# Relay-Board_Rack-PDU_1_0.net
KiCad netlist of a schematic drawn in EAGLE
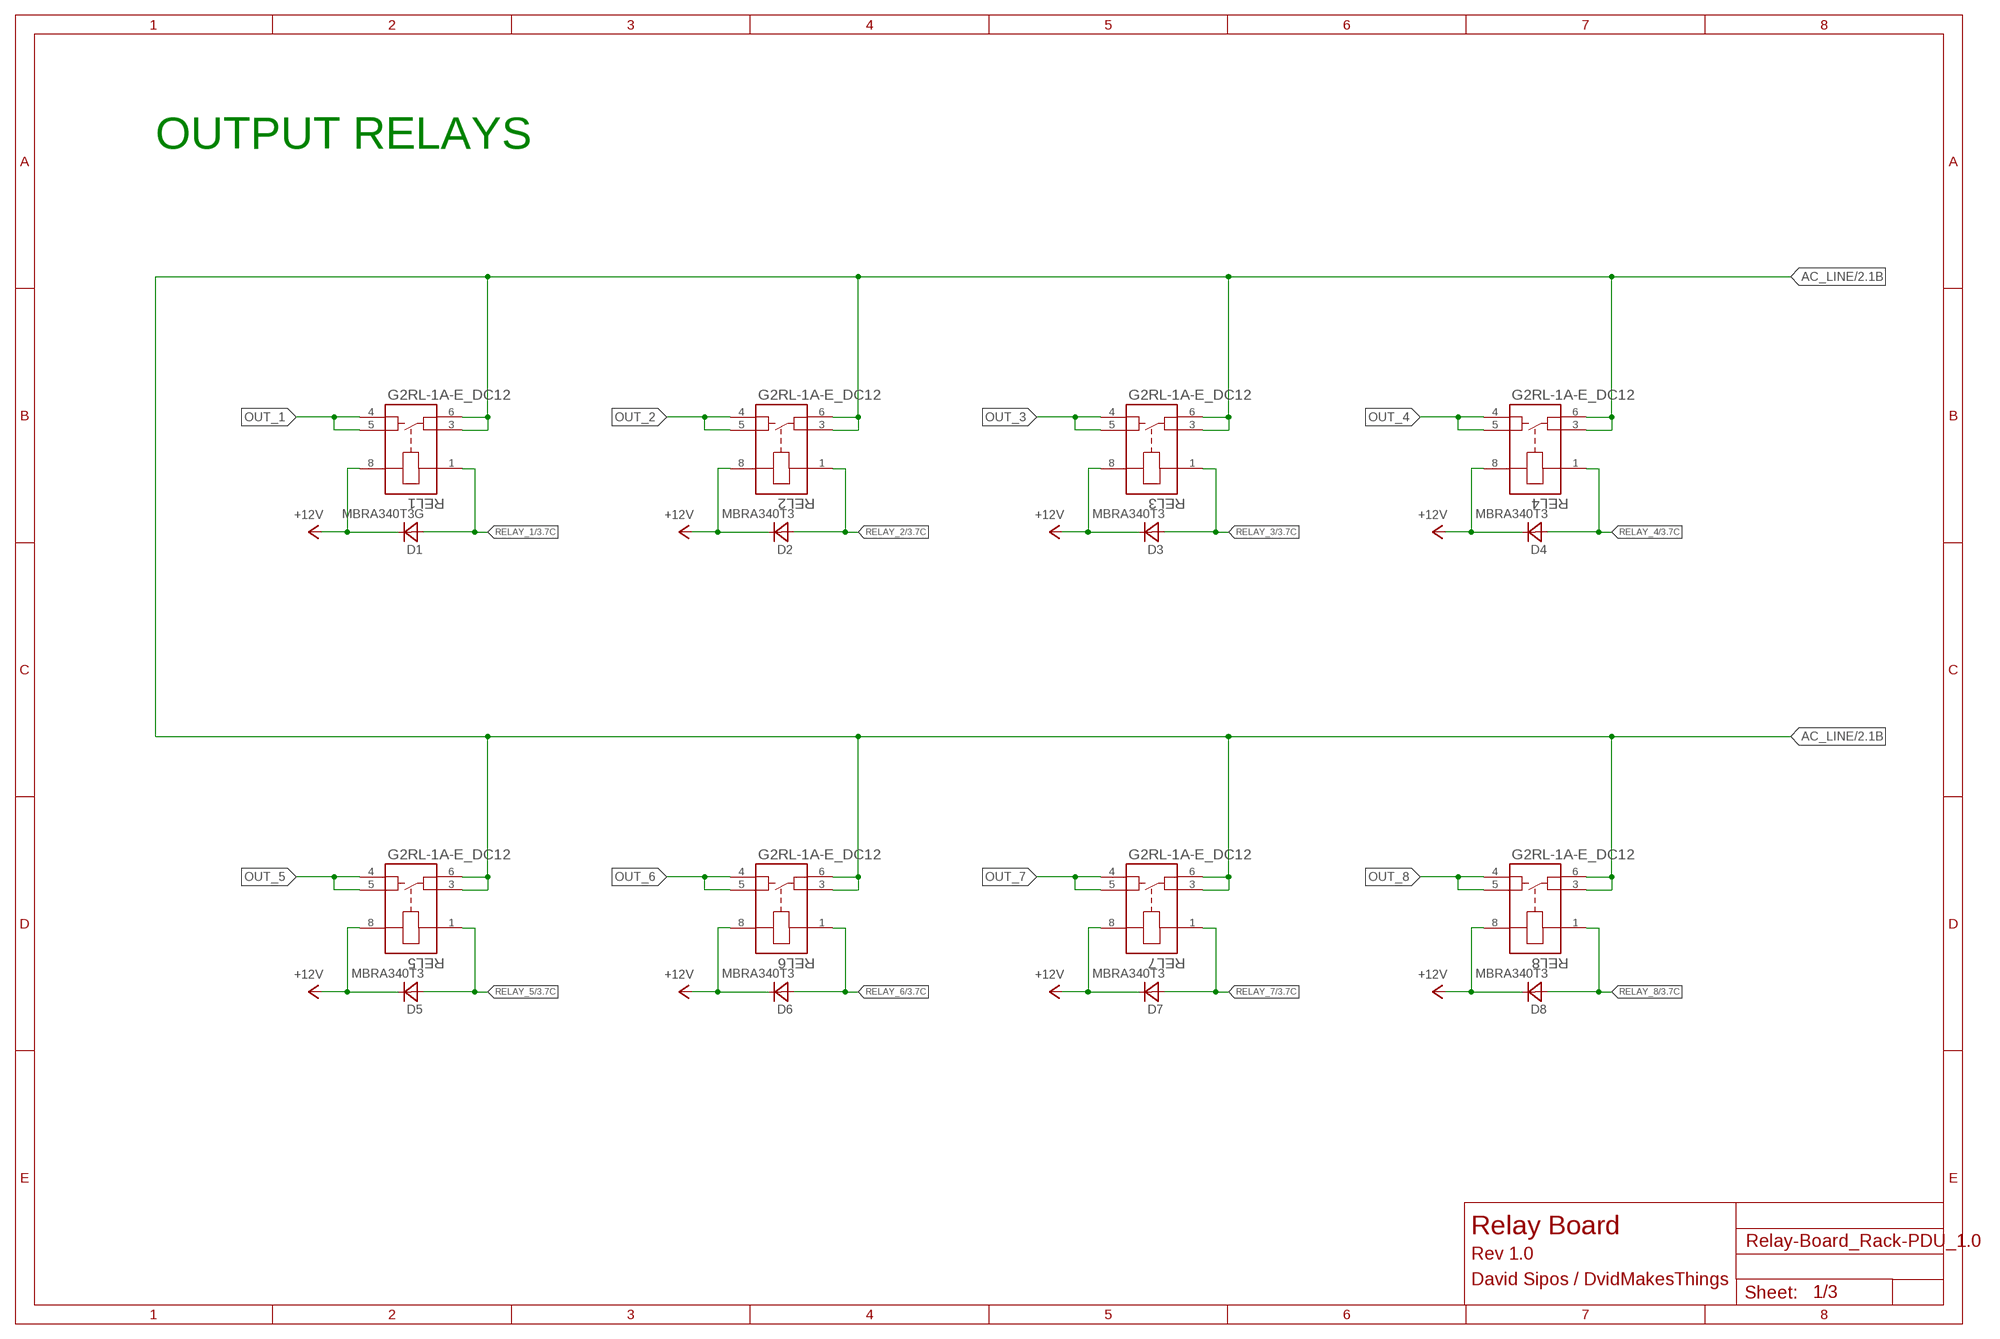
[diagram p0: schematic, sheet 1]
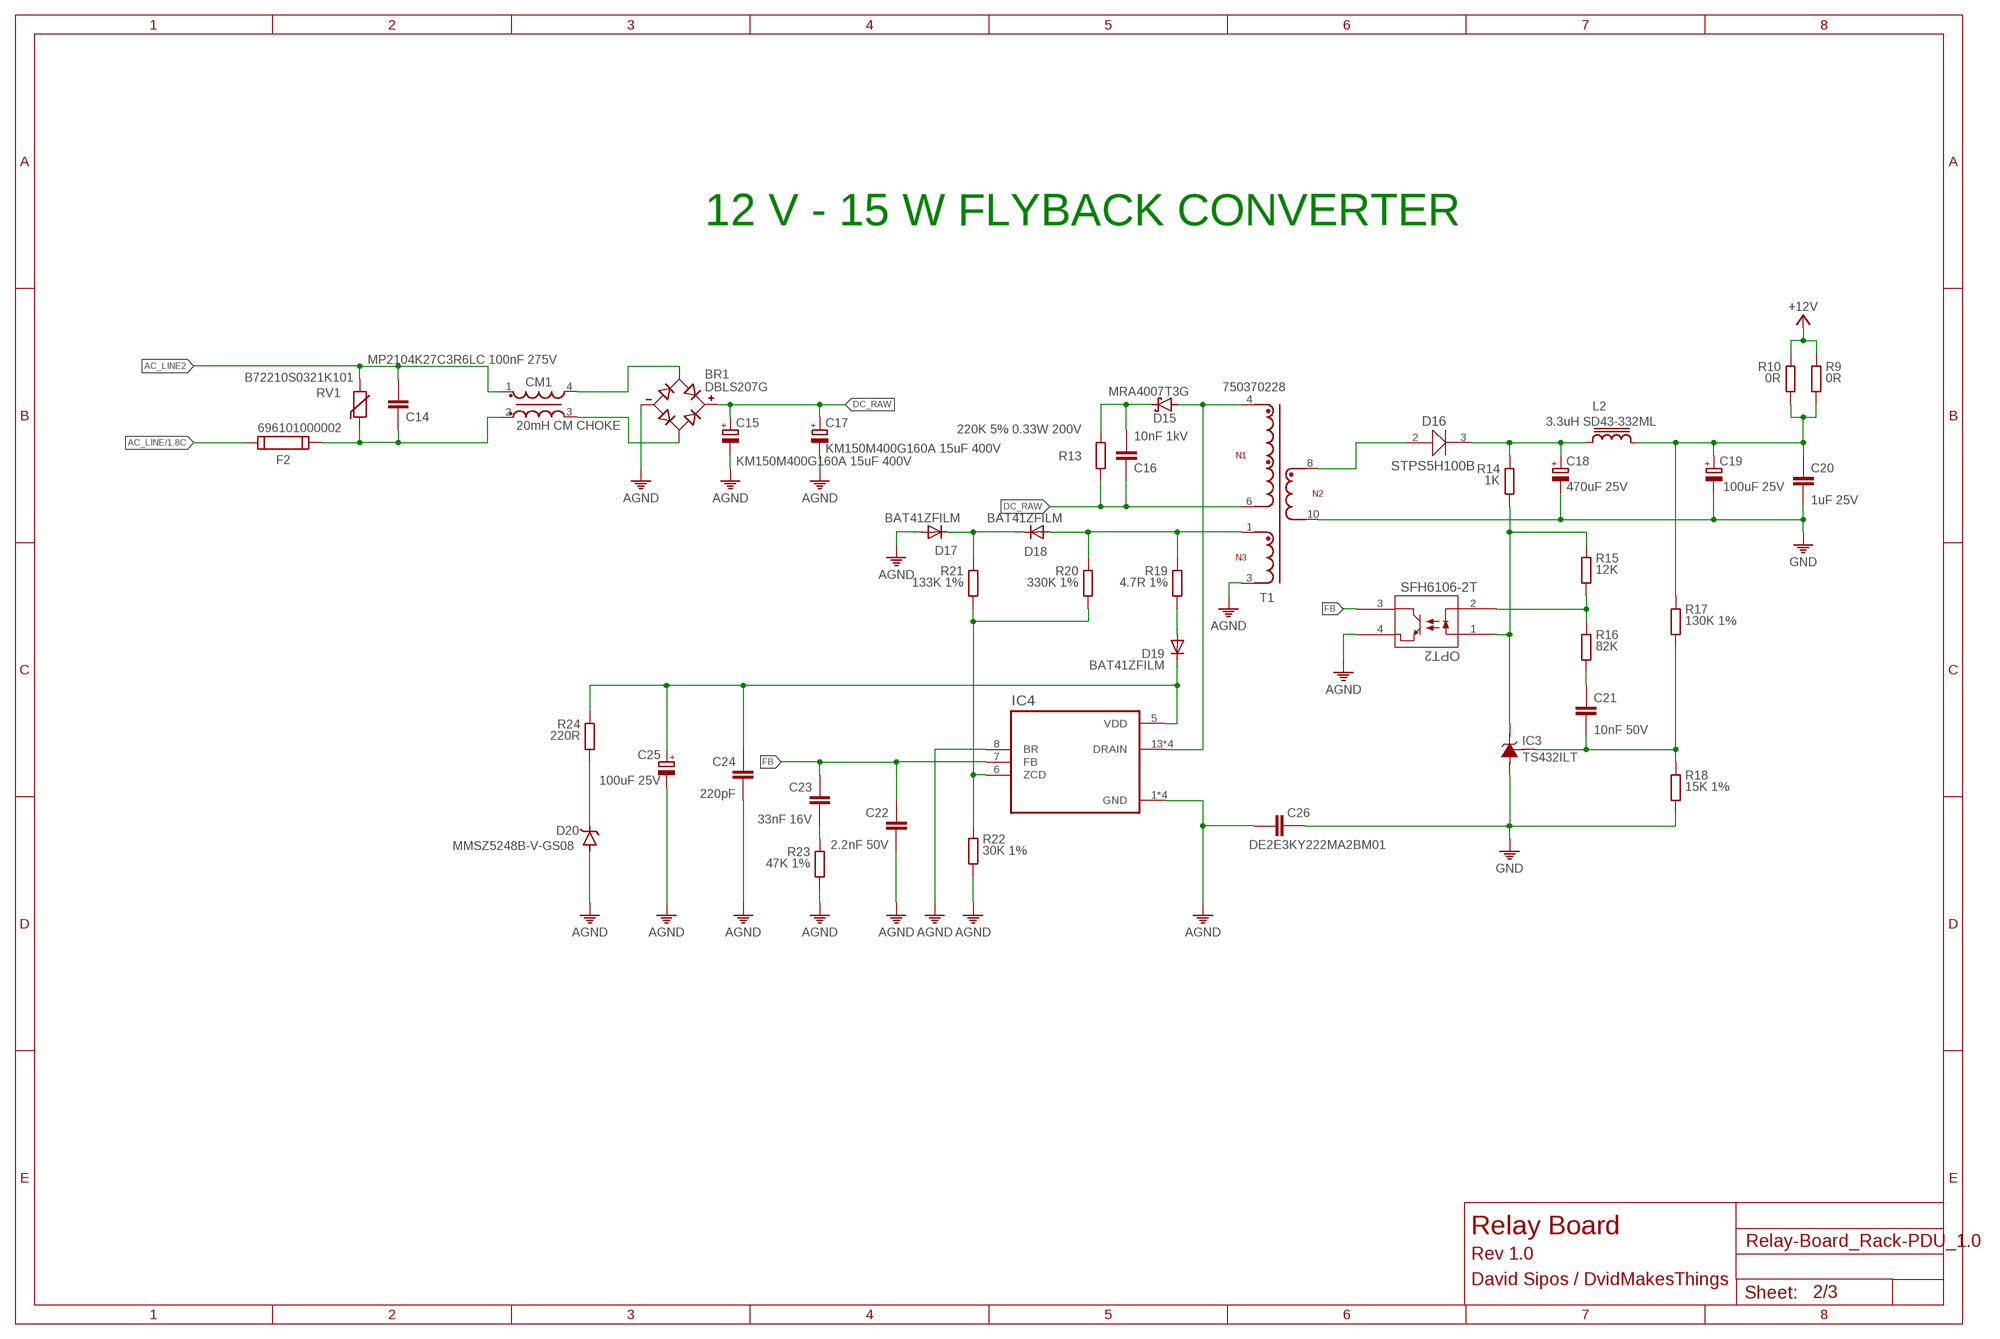
[diagram p1: schematic, sheet 2]
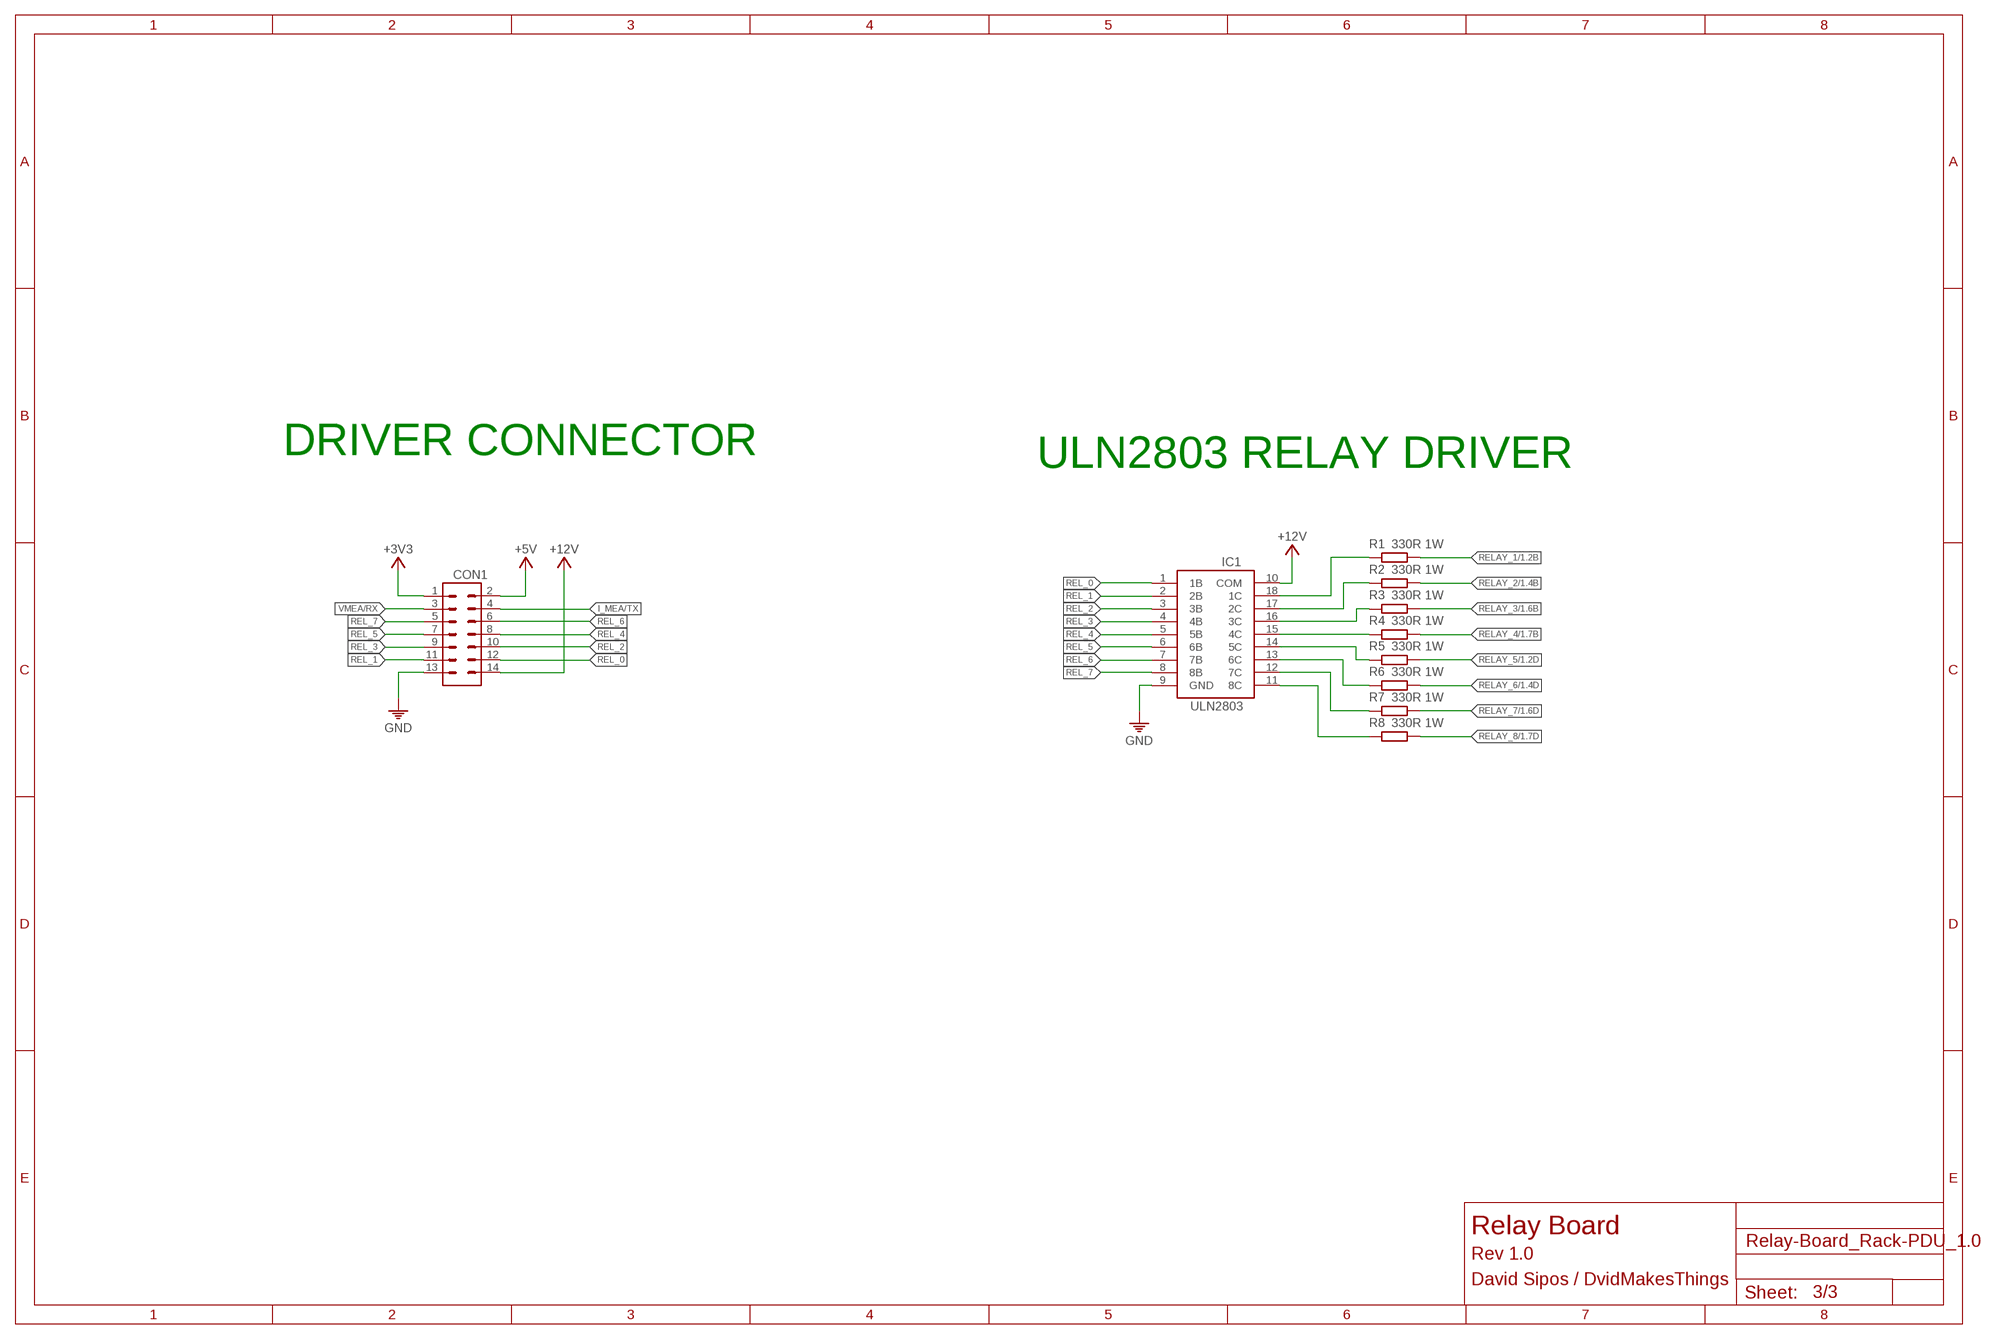
[diagram p2: schematic, sheet 3]

(export (version "E")
  (design (tool "Eeschema 10.0.6"))
  (components
    (comp (ref "D1")
      (value "MBRA340T3G")
      (footprint "eagle-import:SMA")
      (libsource (lib "eagle-import") (part "MBRA340T3"))
    )
    (comp (ref "D2")
      (value "MBRA340T3")
      (footprint "eagle-import:SMA")
      (libsource (lib "eagle-import") (part "MBRA340T3"))
    )
    (comp (ref "D3")
      (value "MBRA340T3")
      (footprint "eagle-import:SMA")
      (libsource (lib "eagle-import") (part "MBRA340T3"))
    )
    (comp (ref "D4")
      (value "MBRA340T3")
      (footprint "eagle-import:SMA")
      (libsource (lib "eagle-import") (part "MBRA340T3"))
    )
    (comp (ref "D5")
      (value "MBRA340T3")
      (footprint "eagle-import:SMA")
      (libsource (lib "eagle-import") (part "MBRA340T3"))
    )
    (comp (ref "D6")
      (value "MBRA340T3")
      (footprint "eagle-import:SMA")
      (libsource (lib "eagle-import") (part "MBRA340T3"))
    )
    (comp (ref "D7")
      (value "MBRA340T3")
      (footprint "eagle-import:SMA")
      (libsource (lib "eagle-import") (part "MBRA340T3"))
    )
    (comp (ref "D8")
      (value "MBRA340T3")
      (footprint "eagle-import:SMA")
      (libsource (lib "eagle-import") (part "MBRA340T3"))
    )
    (comp (ref "REL1")
      (value "G2RL-1A-E_DC12")
      (footprint "eagle-import:RELAY_G2RL-1A-E_DC5_OMR")
      (fields
        (field (name "MANUFACTURER_PART_NUMBER") "G2RL-1A-E DC12")
        (field (name "COPYRIGHT") "Copyright (C) 2025 Ultra Librarian. All rights reserved.")
      )
      (libsource (lib "eagle-import") (part "G2RL-1A-E_DC12"))
    )
    (comp (ref "REL2")
      (value "G2RL-1A-E_DC12")
      (footprint "eagle-import:RELAY_G2RL-1A-E_DC5_OMR")
      (fields
        (field (name "MANUFACTURER_PART_NUMBER") "G2RL-1A-E DC12")
        (field (name "COPYRIGHT") "Copyright (C) 2025 Ultra Librarian. All rights reserved.")
      )
      (libsource (lib "eagle-import") (part "G2RL-1A-E_DC12"))
    )
    (comp (ref "REL3")
      (value "G2RL-1A-E_DC12")
      (footprint "eagle-import:RELAY_G2RL-1A-E_DC5_OMR")
      (fields
        (field (name "MANUFACTURER_PART_NUMBER") "G2RL-1A-E DC12")
        (field (name "COPYRIGHT") "Copyright (C) 2025 Ultra Librarian. All rights reserved.")
      )
      (libsource (lib "eagle-import") (part "G2RL-1A-E_DC12"))
    )
    (comp (ref "REL4")
      (value "G2RL-1A-E_DC12")
      (footprint "eagle-import:RELAY_G2RL-1A-E_DC5_OMR")
      (fields
        (field (name "MANUFACTURER_PART_NUMBER") "G2RL-1A-E DC12")
        (field (name "COPYRIGHT") "Copyright (C) 2025 Ultra Librarian. All rights reserved.")
      )
      (libsource (lib "eagle-import") (part "G2RL-1A-E_DC12"))
    )
    (comp (ref "REL5")
      (value "G2RL-1A-E_DC12")
      (footprint "eagle-import:RELAY_G2RL-1A-E_DC5_OMR")
      (fields
        (field (name "MANUFACTURER_PART_NUMBER") "G2RL-1A-E DC12")
        (field (name "COPYRIGHT") "Copyright (C) 2025 Ultra Librarian. All rights reserved.")
      )
      (libsource (lib "eagle-import") (part "G2RL-1A-E_DC12"))
    )
    (comp (ref "REL6")
      (value "G2RL-1A-E_DC12")
      (footprint "eagle-import:RELAY_G2RL-1A-E_DC5_OMR")
      (fields
        (field (name "MANUFACTURER_PART_NUMBER") "G2RL-1A-E DC12")
        (field (name "COPYRIGHT") "Copyright (C) 2025 Ultra Librarian. All rights reserved.")
      )
      (libsource (lib "eagle-import") (part "G2RL-1A-E_DC12"))
    )
    (comp (ref "REL7")
      (value "G2RL-1A-E_DC12")
      (footprint "eagle-import:RELAY_G2RL-1A-E_DC5_OMR")
      (fields
        (field (name "MANUFACTURER_PART_NUMBER") "G2RL-1A-E DC12")
        (field (name "COPYRIGHT") "Copyright (C) 2025 Ultra Librarian. All rights reserved.")
      )
      (libsource (lib "eagle-import") (part "G2RL-1A-E_DC12"))
    )
    (comp (ref "REL8")
      (value "G2RL-1A-E_DC12")
      (footprint "eagle-import:RELAY_G2RL-1A-E_DC5_OMR")
      (fields
        (field (name "MANUFACTURER_PART_NUMBER") "G2RL-1A-E DC12")
        (field (name "COPYRIGHT") "Copyright (C) 2025 Ultra Librarian. All rights reserved.")
      )
      (libsource (lib "eagle-import") (part "G2RL-1A-E_DC12"))
    )
    (comp (ref "BR1")
      (value "DBLS207G")
      (footprint "eagle-import:DIOB_DBLS207G")
      (fields (field (name "MANUFACTURER") "Taiwan Semiconductor"))
      (libsource (lib "eagle-import") (part "DBLS207G"))
    )
    (comp (ref "C14")
      (value "MP2104K27C3R6LC 100nF 275V")
      (footprint "eagle-import:103-275V")
      (libsource (lib "eagle-import") (part "C"))
    )
    (comp (ref "C15")
      (value "KM150M400G160A 15uF 400V")
      (footprint "eagle-import:CAPPRD550W110D1250H2500B")
      (libsource (lib "eagle-import") (part "C-POLRADIAL-25MM-DIA_"))
    )
    (comp (ref "C16")
      (value "10nF 1kV")
      (footprint "eagle-import:C1206")
      (libsource (lib "eagle-import") (part "C-1206"))
    )
    (comp (ref "C17")
      (value "KM150M400G160A 15uF 400V")
      (footprint "eagle-import:CAPPRD550W110D1250H2500B")
      (libsource (lib "eagle-import") (part "C-POLRADIAL-25MM-DIA_"))
    )
    (comp (ref "C18")
      (value "470uF 25V")
      (footprint "eagle-import:CAPPRD508W65D1000H1100B")
      (libsource (lib "eagle-import") (part "C-POLRADIAL-11MM-DIA_"))
    )
    (comp (ref "C19")
      (value "100uF 25V")
      (footprint "eagle-import:CAPPRD508W65D1000H1100B")
      (libsource (lib "eagle-import") (part "C-POLRADIAL-11MM-DIA_"))
    )
    (comp (ref "C20")
      (value "1uF 25V")
      (footprint "eagle-import:C0805")
      (libsource (lib "eagle-import") (part "C-0805"))
    )
    (comp (ref "C21")
      (value "10nF 50V")
      (footprint "eagle-import:C0805")
      (libsource (lib "eagle-import") (part "C-0805"))
    )
    (comp (ref "C22")
      (value "2.2nF 50V")
      (footprint "eagle-import:C0603")
      (libsource (lib "eagle-import") (part "C-0603"))
    )
    (comp (ref "C23")
      (value "33nF 16V")
      (footprint "eagle-import:C0603")
      (libsource (lib "eagle-import") (part "C-0603"))
    )
    (comp (ref "C24")
      (value "220pF")
      (footprint "eagle-import:C0805")
      (libsource (lib "eagle-import") (part "C-0805"))
    )
    (comp (ref "C25")
      (value "100uF 25V")
      (footprint "eagle-import:CAPPRD508W65D1000H1100B")
      (libsource (lib "eagle-import") (part "C-POLRADIAL-11MM-DIA_"))
    )
    (comp (ref "C26")
      (value "DE2E3KY222MA2BM01")
      (footprint "eagle-import:AR21AC103K4R")
      (libsource (lib "eagle-import") (part "C102-1KV"))
    )
    (comp (ref "CM1")
      (value "20mH CM CHOKE")
      (footprint "eagle-import:WE-CMB_XS_744821120")
      (libsource (lib "eagle-import") (part "WE-CMB_XS_744821120"))
    )
    (comp (ref "D15")
      (value "MRA4007T3G")
      (footprint "eagle-import:SMA")
      (fields
        (field (name "DIGIKEY_PART_NUMBER") "SS12FSCT-ND")
        (field (name "MANUFACTURER") "ON Semiconductor")
        (field (name "MPN") "SS12")
        (field (name "CREATED_BY") "PCBLayout.com")
      )
      (libsource (lib "eagle-import") (part "SS12"))
    )
    (comp (ref "D16")
      (value "STPS5H100B")
      (footprint "eagle-import:DPAK_STM")
      (fields (field (name "COPYRIGHT") "Copyright (C) 2025 Ultra Librarian. All rights reserved."))
      (libsource (lib "eagle-import") (part "STPS5H100B"))
    )
    (comp (ref "D17")
      (value "BAT41ZFILM")
      (footprint "eagle-import:SOD-123_MINI-SMA")
      (libsource (lib "eagle-import") (part "CGRM400-G1"))
    )
    (comp (ref "D18")
      (value "BAT41ZFILM")
      (footprint "eagle-import:SOD-123_MINI-SMA")
      (libsource (lib "eagle-import") (part "CGRM400-G1"))
    )
    (comp (ref "D19")
      (value "BAT41ZFILM")
      (footprint "eagle-import:SOD-123_MINI-SMA")
      (libsource (lib "eagle-import") (part "CGRM400-G1"))
    )
    (comp (ref "D20")
      (value "MMSZ5248B-V-GS08")
      (footprint "eagle-import:DO214AC")
      (fields
        (field (name "DIGIKEY_PARTNO") "BZG03C240-HM3-08GICT-ND")
        (field (name "MANUFACTURER") "Vishay General Semiconductor - Diodes Division")
        (field (name "MPN") "BZG03C240-HM3-08")
        (field (name "CREATED_BY") "PCBLayout.om")
      )
      (libsource (lib "eagle-import") (part "BZG03C240-HM3-08"))
    )
    (comp (ref "F2")
      (value "696101000002")
      (footprint "eagle-import:696101000002")
      (libsource (lib "eagle-import") (part "696101000002"))
    )
    (comp (ref "IC3")
      (value "TS432ILT")
      (footprint "eagle-import:SOT23")
      (libsource (lib "eagle-import") (part "TS432ILT"))
    )
    (comp (ref "IC4")
      (value "VIPER35HD")
      (footprint "eagle-import:VIPER35HD")
      (libsource (lib "eagle-import") (part "VIPER35HD"))
    )
    (comp (ref "L2")
      (value "3.3uH SD43-332ML")
      (footprint "eagle-import:INDUCTOR-BOURNS_SRN8040")
      (libsource (lib "eagle-import") (part "INDUCTOR-BOURNS_SRN8040"))
    )
    (comp (ref "OPT2")
      (value "SFH6106-2T")
      (footprint "eagle-import:SMD-4_SFH610X_VIS-M")
      (fields
        (field (name "MANUFACTURER_PART_NUMBER") "SFH6106-3")
        (field (name "COPYRIGHT") "Copyright (C) 2025 Ultra Librarian. All rights reserved.")
      )
      (libsource (lib "eagle-import") (part "SFH6106-3SMD-4_SFH610X_VIS-M"))
    )
    (comp (ref "R9")
      (value "0R")
      (footprint "eagle-import:0805")
      (libsource (lib "eagle-import") (part "R0805"))
    )
    (comp (ref "R10")
      (value "0R")
      (footprint "eagle-import:0805")
      (libsource (lib "eagle-import") (part "R0805"))
    )
    (comp (ref "R13")
      (value "220K 5% 0.33W 200V")
      (footprint "eagle-import:1206")
      (libsource (lib "eagle-import") (part "R1206"))
    )
    (comp (ref "R14")
      (value "1K")
      (footprint "eagle-import:0603")
      (libsource (lib "eagle-import") (part "R0603"))
    )
    (comp (ref "R15")
      (value "12K")
      (footprint "eagle-import:0603")
      (libsource (lib "eagle-import") (part "R0603"))
    )
    (comp (ref "R16")
      (value "82K")
      (footprint "eagle-import:0603")
      (libsource (lib "eagle-import") (part "R0603"))
    )
    (comp (ref "R17")
      (value "130K 1%")
      (footprint "eagle-import:0603")
      (libsource (lib "eagle-import") (part "R0603"))
    )
    (comp (ref "R18")
      (value "15K 1%")
      (footprint "eagle-import:0603")
      (libsource (lib "eagle-import") (part "R0603"))
    )
    (comp (ref "R19")
      (value "4.7R 1%")
      (footprint "eagle-import:0603")
      (libsource (lib "eagle-import") (part "R0603"))
    )
    (comp (ref "R20")
      (value "330K 1%")
      (footprint "eagle-import:0603")
      (libsource (lib "eagle-import") (part "R0603"))
    )
    (comp (ref "R21")
      (value "133K 1%")
      (footprint "eagle-import:0603")
      (libsource (lib "eagle-import") (part "R0603"))
    )
    (comp (ref "R22")
      (value "30K 1%")
      (footprint "eagle-import:0603")
      (libsource (lib "eagle-import") (part "R0603"))
    )
    (comp (ref "R23")
      (value "47K 1%")
      (footprint "eagle-import:0603")
      (libsource (lib "eagle-import") (part "R0603"))
    )
    (comp (ref "R24")
      (value "220R")
      (footprint "eagle-import:0805")
      (libsource (lib "eagle-import") (part "R0805"))
    )
    (comp (ref "RV1")
      (value "B72210S0321K101")
      (footprint "eagle-import:WE-VD_10MM_820412001")
      (libsource (lib "eagle-import") (part "WE-VD_10MM_820412001"))
    )
    (comp (ref "T1")
      (value "750370228")
      (footprint "eagle-import:WE-OLSTM_EE20_L22.2W25H16")
      (libsource (lib "eagle-import") (part "750370228"))
    )
    (comp (ref "CON1")
      (value "CON-2X7")
      (footprint "eagle-import:2X7")
      (libsource (lib "eagle-import") (part "CON-2X7"))
    )
    (comp (ref "IC1")
      (value "ULN2803A")
      (footprint "eagle-import:SO18")
      (libsource (lib "eagle-import") (part "ULN2803"))
    )
    (comp (ref "R1")
      (value "330R 1W")
      (footprint "eagle-import:1206")
      (libsource (lib "eagle-import") (part "R1206"))
    )
    (comp (ref "R2")
      (value "330R 1W")
      (footprint "eagle-import:1206")
      (libsource (lib "eagle-import") (part "R1206"))
    )
    (comp (ref "R3")
      (value "330R 1W")
      (footprint "eagle-import:1206")
      (libsource (lib "eagle-import") (part "R1206"))
    )
    (comp (ref "R4")
      (value "330R 1W")
      (footprint "eagle-import:1206")
      (libsource (lib "eagle-import") (part "R1206"))
    )
    (comp (ref "R5")
      (value "330R 1W")
      (footprint "eagle-import:1206")
      (libsource (lib "eagle-import") (part "R1206"))
    )
    (comp (ref "R6")
      (value "330R 1W")
      (footprint "eagle-import:1206")
      (libsource (lib "eagle-import") (part "R1206"))
    )
    (comp (ref "R7")
      (value "330R 1W")
      (footprint "eagle-import:1206")
      (libsource (lib "eagle-import") (part "R1206"))
    )
    (comp (ref "R8")
      (value "330R 1W")
      (footprint "eagle-import:1206")
      (libsource (lib "eagle-import") (part "R1206"))
    )
  )
  (nets
    (net (code "1") (name "+3V3") (class "Default")
      (node (ref "CON1") (pin "1") (pinfunction "1_1") (pintype "bidirectional"))
    )
    (net (code "2") (name "+5V") (class "Default")
      (node (ref "CON1") (pin "2") (pinfunction "2_2") (pintype "bidirectional"))
    )
    (net (code "3") (name "+12V") (class "Default")
      (node (ref "CON1") (pin "14") (pinfunction "14_14") (pintype "bidirectional"))
      (node (ref "D1") (pin "C") (pinfunction "C_C") (pintype "passive"))
      (node (ref "D2") (pin "C") (pinfunction "C_C") (pintype "passive"))
      (node (ref "D3") (pin "C") (pinfunction "C_C") (pintype "passive"))
      (node (ref "D4") (pin "C") (pinfunction "C_C") (pintype "passive"))
      (node (ref "D5") (pin "C") (pinfunction "C_C") (pintype "passive"))
      (node (ref "D6") (pin "C") (pinfunction "C_C") (pintype "passive"))
      (node (ref "D7") (pin "C") (pinfunction "C_C") (pintype "passive"))
      (node (ref "D8") (pin "C") (pinfunction "C_C") (pintype "passive"))
      (node (ref "IC1") (pin "10") (pinfunction "COM_10") (pintype "bidirectional"))
      (node (ref "R10") (pin "1") (pinfunction "1_1") (pintype "passive"))
      (node (ref "R9") (pin "1") (pinfunction "1_1") (pintype "passive"))
      (node (ref "REL1") (pin "8") (pinfunction "8_8") (pintype "passive"))
      (node (ref "REL2") (pin "8") (pinfunction "8_8") (pintype "passive"))
      (node (ref "REL3") (pin "8") (pinfunction "8_8") (pintype "passive"))
      (node (ref "REL4") (pin "8") (pinfunction "8_8") (pintype "passive"))
      (node (ref "REL5") (pin "8") (pinfunction "8_8") (pintype "passive"))
      (node (ref "REL6") (pin "8") (pinfunction "8_8") (pintype "passive"))
      (node (ref "REL7") (pin "8") (pinfunction "8_8") (pintype "passive"))
      (node (ref "REL8") (pin "8") (pinfunction "8_8") (pintype "passive"))
    )
    (net (code "4") (name "AC_LINE") (class "Default")
      (node (ref "F2") (pin "1") (pinfunction "1_1") (pintype "passive"))
      (node (ref "REL1") (pin "3") (pinfunction "3_3") (pintype "passive"))
      (node (ref "REL1") (pin "6") (pinfunction "6_6") (pintype "passive"))
      (node (ref "REL2") (pin "3") (pinfunction "3_3") (pintype "passive"))
      (node (ref "REL2") (pin "6") (pinfunction "6_6") (pintype "passive"))
      (node (ref "REL3") (pin "3") (pinfunction "3_3") (pintype "passive"))
      (node (ref "REL3") (pin "6") (pinfunction "6_6") (pintype "passive"))
      (node (ref "REL4") (pin "3") (pinfunction "3_3") (pintype "passive"))
      (node (ref "REL4") (pin "6") (pinfunction "6_6") (pintype "passive"))
      (node (ref "REL5") (pin "3") (pinfunction "3_3") (pintype "passive"))
      (node (ref "REL5") (pin "6") (pinfunction "6_6") (pintype "passive"))
      (node (ref "REL6") (pin "3") (pinfunction "3_3") (pintype "passive"))
      (node (ref "REL6") (pin "6") (pinfunction "6_6") (pintype "passive"))
      (node (ref "REL7") (pin "3") (pinfunction "3_3") (pintype "passive"))
      (node (ref "REL7") (pin "6") (pinfunction "6_6") (pintype "passive"))
      (node (ref "REL8") (pin "3") (pinfunction "3_3") (pintype "passive"))
      (node (ref "REL8") (pin "6") (pinfunction "6_6") (pintype "passive"))
    )
    (net (code "5") (name "AC_LINE2") (class "Default")
      (node (ref "C14") (pin "2") (pinfunction "2_2") (pintype "passive"))
      (node (ref "CM1") (pin "1") (pinfunction "1_1") (pintype "passive"))
      (node (ref "RV1") (pin "2") (pinfunction "2_2") (pintype "passive"))
    )
    (net (code "6") (name "AGND") (class "Default")
      (node (ref "BR1") (pin "-") (pinfunction "-_-") (pintype "passive"))
      (node (ref "C15") (pin "2") (pinfunction "-_2") (pintype "passive"))
      (node (ref "C17") (pin "2") (pinfunction "-_2") (pintype "passive"))
      (node (ref "C22") (pin "2") (pinfunction "2_2") (pintype "passive"))
      (node (ref "C24") (pin "2") (pinfunction "2_2") (pintype "passive"))
      (node (ref "C25") (pin "2") (pinfunction "-_2") (pintype "passive"))
      (node (ref "C26") (pin "1") (pinfunction "1_1") (pintype "passive"))
      (node (ref "D17") (pin "A") (pinfunction "A_A") (pintype "passive"))
      (node (ref "D20") (pin "A") (pinfunction "A_A") (pintype "passive"))
      (node (ref "IC4") (pin "1") (pinfunction "GND_1") (pintype "power_in"))
      (node (ref "IC4") (pin "2") (pinfunction "GND_2") (pintype "power_in"))
      (node (ref "IC4") (pin "3") (pinfunction "GND_3") (pintype "power_in"))
      (node (ref "IC4") (pin "4") (pinfunction "GND_4") (pintype "power_in"))
      (node (ref "IC4") (pin "8") (pinfunction "BR_8") (pintype "input"))
      (node (ref "OPT2") (pin "4") (pinfunction "4_4") (pintype "passive"))
      (node (ref "R22") (pin "2") (pinfunction "2_2") (pintype "passive"))
      (node (ref "R23") (pin "2") (pinfunction "2_2") (pintype "passive"))
      (node (ref "T1") (pin "3") (pinfunction "3_3") (pintype "passive"))
    )
    (net (code "7") (name "DC_RAW") (class "Default")
      (node (ref "BR1") (pin "+") (pinfunction "+_+") (pintype "passive"))
      (node (ref "C15") (pin "1") (pinfunction "+_1") (pintype "passive"))
      (node (ref "C16") (pin "1") (pinfunction "1_1") (pintype "passive"))
      (node (ref "C17") (pin "1") (pinfunction "+_1") (pintype "passive"))
      (node (ref "R13") (pin "2") (pinfunction "2_2") (pintype "passive"))
      (node (ref "T1") (pin "6") (pinfunction "6_6") (pintype "passive"))
    )
    (net (code "8") (name "FB") (class "Default")
      (node (ref "C22") (pin "1") (pinfunction "1_1") (pintype "passive"))
      (node (ref "C23") (pin "1") (pinfunction "1_1") (pintype "passive"))
      (node (ref "IC4") (pin "7") (pinfunction "FB_7") (pintype "input"))
      (node (ref "OPT2") (pin "3") (pinfunction "3_3") (pintype "passive"))
    )
    (net (code "9") (name "GND") (class "Default")
      (node (ref "C18") (pin "2") (pinfunction "-_2") (pintype "passive"))
      (node (ref "C19") (pin "2") (pinfunction "-_2") (pintype "passive"))
      (node (ref "C20") (pin "2") (pinfunction "2_2") (pintype "passive"))
      (node (ref "C26") (pin "2") (pinfunction "2_2") (pintype "passive"))
      (node (ref "CON1") (pin "13") (pinfunction "13_13") (pintype "bidirectional"))
      (node (ref "IC1") (pin "9") (pinfunction "GND_9") (pintype "bidirectional"))
      (node (ref "IC3") (pin "3") (pinfunction "3_3") (pintype "bidirectional"))
      (node (ref "R18") (pin "2") (pinfunction "2_2") (pintype "passive"))
      (node (ref "T1") (pin "10") (pinfunction "10_10") (pintype "passive"))
    )
    (net (code "10") (name "I_MEA{slash}TX") (class "Default")
      (node (ref "CON1") (pin "4") (pinfunction "4_4") (pintype "bidirectional"))
    )
    (net (code "11") (name "Net-(BR1-PadAC1)") (class "Default")
      (node (ref "BR1") (pin "AC1") (pinfunction "AC1_AC1") (pintype "passive"))
      (node (ref "CM1") (pin "4") (pinfunction "4_4") (pintype "passive"))
    )
    (net (code "12") (name "Net-(BR1-PadAC2)") (class "Default")
      (node (ref "BR1") (pin "AC2") (pinfunction "AC2_AC2") (pintype "passive"))
      (node (ref "CM1") (pin "3") (pinfunction "3_3") (pintype "passive"))
    )
    (net (code "13") (name "Net-(C14-Pad1)") (class "Default")
      (node (ref "C14") (pin "1") (pinfunction "1_1") (pintype "passive"))
      (node (ref "CM1") (pin "2") (pinfunction "2_2") (pintype "passive"))
      (node (ref "F2") (pin "2") (pinfunction "2_2") (pintype "passive"))
      (node (ref "RV1") (pin "1") (pinfunction "1_1") (pintype "passive"))
    )
    (net (code "14") (name "Net-(C16-Pad2)") (class "Default")
      (node (ref "C16") (pin "2") (pinfunction "2_2") (pintype "passive"))
      (node (ref "D15") (pin "C") (pinfunction "C_C") (pintype "passive"))
      (node (ref "R13") (pin "1") (pinfunction "1_1") (pintype "passive"))
    )
    (net (code "15") (name "Net-(C18-+)") (class "Default")
      (node (ref "C18") (pin "1") (pinfunction "+_1") (pintype "passive"))
      (node (ref "D16") (pin "3") (pinfunction "3_3") (pintype "passive"))
      (node (ref "L2") (pin "1") (pinfunction "1_1") (pintype "passive"))
      (node (ref "R14") (pin "1") (pinfunction "1_1") (pintype "passive"))
    )
    (net (code "16") (name "Net-(C19-+)") (class "Default")
      (node (ref "C19") (pin "1") (pinfunction "+_1") (pintype "passive"))
      (node (ref "C20") (pin "1") (pinfunction "1_1") (pintype "passive"))
      (node (ref "L2") (pin "2") (pinfunction "2_2") (pintype "passive"))
      (node (ref "R10") (pin "2") (pinfunction "2_2") (pintype "passive"))
      (node (ref "R17") (pin "1") (pinfunction "1_1") (pintype "passive"))
      (node (ref "R9") (pin "2") (pinfunction "2_2") (pintype "passive"))
    )
    (net (code "17") (name "Net-(C21-Pad1)") (class "Default")
      (node (ref "C21") (pin "1") (pinfunction "1_1") (pintype "passive"))
      (node (ref "R16") (pin "2") (pinfunction "2_2") (pintype "passive"))
    )
    (net (code "18") (name "Net-(C21-Pad2)") (class "Default")
      (node (ref "C21") (pin "2") (pinfunction "2_2") (pintype "passive"))
      (node (ref "IC3") (pin "1") (pinfunction "1_1") (pintype "bidirectional"))
      (node (ref "R17") (pin "2") (pinfunction "2_2") (pintype "passive"))
      (node (ref "R18") (pin "1") (pinfunction "1_1") (pintype "passive"))
    )
    (net (code "19") (name "Net-(C23-Pad2)") (class "Default")
      (node (ref "C23") (pin "2") (pinfunction "2_2") (pintype "passive"))
      (node (ref "R23") (pin "1") (pinfunction "1_1") (pintype "passive"))
    )
    (net (code "20") (name "Net-(C25-+)") (class "Default")
      (node (ref "C24") (pin "1") (pinfunction "1_1") (pintype "passive"))
      (node (ref "C25") (pin "1") (pinfunction "+_1") (pintype "passive"))
      (node (ref "D19") (pin "C") (pinfunction "C_C") (pintype "passive"))
      (node (ref "IC4") (pin "5") (pinfunction "VDD_5") (pintype "power_in"))
      (node (ref "R24") (pin "1") (pinfunction "1_1") (pintype "passive"))
    )
    (net (code "21") (name "Net-(D15-PadA)") (class "Default")
      (node (ref "D15") (pin "A") (pinfunction "A_A") (pintype "passive"))
      (node (ref "IC4") (pin "13") (pinfunction "DRAIN_13") (pintype "output"))
      (node (ref "IC4") (pin "14") (pinfunction "DRAIN_14") (pintype "output"))
      (node (ref "IC4") (pin "15") (pinfunction "DRAIN_15") (pintype "output"))
      (node (ref "IC4") (pin "16") (pinfunction "DRAIN_16") (pintype "output"))
      (node (ref "T1") (pin "4") (pinfunction "4_4") (pintype "passive"))
    )
    (net (code "22") (name "Net-(D16-Pad2)") (class "Default")
      (node (ref "D16") (pin "2") (pinfunction "2_2") (pintype "passive"))
      (node (ref "T1") (pin "8") (pinfunction "8_8") (pintype "passive"))
    )
    (net (code "23") (name "Net-(D17-PadC)") (class "Default")
      (node (ref "D17") (pin "C") (pinfunction "C_C") (pintype "passive"))
      (node (ref "D18") (pin "C") (pinfunction "C_C") (pintype "passive"))
      (node (ref "R21") (pin "1") (pinfunction "1_1") (pintype "passive"))
    )
    (net (code "24") (name "Net-(D18-PadA)") (class "Default")
      (node (ref "D18") (pin "A") (pinfunction "A_A") (pintype "passive"))
      (node (ref "R19") (pin "1") (pinfunction "1_1") (pintype "passive"))
      (node (ref "R20") (pin "1") (pinfunction "1_1") (pintype "passive"))
      (node (ref "T1") (pin "1") (pinfunction "1_1") (pintype "passive"))
    )
    (net (code "25") (name "Net-(D19-PadA)") (class "Default")
      (node (ref "D19") (pin "A") (pinfunction "A_A") (pintype "passive"))
      (node (ref "R19") (pin "2") (pinfunction "2_2") (pintype "passive"))
    )
    (net (code "26") (name "Net-(D20-PadC)") (class "Default")
      (node (ref "D20") (pin "C") (pinfunction "C_C") (pintype "passive"))
      (node (ref "R24") (pin "2") (pinfunction "2_2") (pintype "passive"))
    )
    (net (code "27") (name "Net-(IC1-1C)") (class "Default")
      (node (ref "IC1") (pin "18") (pinfunction "1C_18") (pintype "bidirectional"))
      (node (ref "R1") (pin "1") (pinfunction "1_1") (pintype "passive"))
    )
    (net (code "28") (name "Net-(IC1-2C)") (class "Default")
      (node (ref "IC1") (pin "17") (pinfunction "2C_17") (pintype "bidirectional"))
      (node (ref "R2") (pin "1") (pinfunction "1_1") (pintype "passive"))
    )
    (net (code "29") (name "Net-(IC1-3C)") (class "Default")
      (node (ref "IC1") (pin "16") (pinfunction "3C_16") (pintype "bidirectional"))
      (node (ref "R3") (pin "1") (pinfunction "1_1") (pintype "passive"))
    )
    (net (code "30") (name "Net-(IC1-4C)") (class "Default")
      (node (ref "IC1") (pin "15") (pinfunction "4C_15") (pintype "bidirectional"))
      (node (ref "R4") (pin "1") (pinfunction "1_1") (pintype "passive"))
    )
    (net (code "31") (name "Net-(IC1-5C)") (class "Default")
      (node (ref "IC1") (pin "14") (pinfunction "5C_14") (pintype "bidirectional"))
      (node (ref "R5") (pin "1") (pinfunction "1_1") (pintype "passive"))
    )
    (net (code "32") (name "Net-(IC1-6C)") (class "Default")
      (node (ref "IC1") (pin "13") (pinfunction "6C_13") (pintype "bidirectional"))
      (node (ref "R6") (pin "1") (pinfunction "1_1") (pintype "passive"))
    )
    (net (code "33") (name "Net-(IC1-7C)") (class "Default")
      (node (ref "IC1") (pin "12") (pinfunction "7C_12") (pintype "bidirectional"))
      (node (ref "R7") (pin "1") (pinfunction "1_1") (pintype "passive"))
    )
    (net (code "34") (name "Net-(IC1-8C)") (class "Default")
      (node (ref "IC1") (pin "11") (pinfunction "8C_11") (pintype "bidirectional"))
      (node (ref "R8") (pin "1") (pinfunction "1_1") (pintype "passive"))
    )
    (net (code "35") (name "Net-(IC3-Pad2)") (class "Default")
      (node (ref "IC3") (pin "2") (pinfunction "2_2") (pintype "bidirectional"))
      (node (ref "OPT2") (pin "1") (pinfunction "1_1") (pintype "passive"))
      (node (ref "R14") (pin "2") (pinfunction "2_2") (pintype "passive"))
      (node (ref "R15") (pin "1") (pinfunction "1_1") (pintype "passive"))
    )
    (net (code "36") (name "Net-(IC4-ZCD)") (class "Default")
      (node (ref "IC4") (pin "6") (pinfunction "ZCD_6") (pintype "input"))
      (node (ref "R20") (pin "2") (pinfunction "2_2") (pintype "passive"))
      (node (ref "R21") (pin "2") (pinfunction "2_2") (pintype "passive"))
      (node (ref "R22") (pin "1") (pinfunction "1_1") (pintype "passive"))
    )
    (net (code "37") (name "Net-(OPT2-Pad2)") (class "Default")
      (node (ref "OPT2") (pin "2") (pinfunction "2_2") (pintype "passive"))
      (node (ref "R15") (pin "2") (pinfunction "2_2") (pintype "passive"))
      (node (ref "R16") (pin "1") (pinfunction "1_1") (pintype "passive"))
    )
    (net (code "38") (name "OUT_1") (class "Default")
      (node (ref "REL1") (pin "4") (pinfunction "4_4") (pintype "passive"))
      (node (ref "REL1") (pin "5") (pinfunction "5_5") (pintype "passive"))
    )
    (net (code "39") (name "OUT_2") (class "Default")
      (node (ref "REL2") (pin "4") (pinfunction "4_4") (pintype "passive"))
      (node (ref "REL2") (pin "5") (pinfunction "5_5") (pintype "passive"))
    )
    (net (code "40") (name "OUT_3") (class "Default")
      (node (ref "REL3") (pin "4") (pinfunction "4_4") (pintype "passive"))
      (node (ref "REL3") (pin "5") (pinfunction "5_5") (pintype "passive"))
    )
    (net (code "41") (name "OUT_4") (class "Default")
      (node (ref "REL4") (pin "4") (pinfunction "4_4") (pintype "passive"))
      (node (ref "REL4") (pin "5") (pinfunction "5_5") (pintype "passive"))
    )
    (net (code "42") (name "OUT_5") (class "Default")
      (node (ref "REL5") (pin "4") (pinfunction "4_4") (pintype "passive"))
      (node (ref "REL5") (pin "5") (pinfunction "5_5") (pintype "passive"))
    )
    (net (code "43") (name "OUT_6") (class "Default")
      (node (ref "REL6") (pin "4") (pinfunction "4_4") (pintype "passive"))
      (node (ref "REL6") (pin "5") (pinfunction "5_5") (pintype "passive"))
    )
    (net (code "44") (name "OUT_7") (class "Default")
      (node (ref "REL7") (pin "4") (pinfunction "4_4") (pintype "passive"))
      (node (ref "REL7") (pin "5") (pinfunction "5_5") (pintype "passive"))
    )
    (net (code "45") (name "OUT_8") (class "Default")
      (node (ref "REL8") (pin "4") (pinfunction "4_4") (pintype "passive"))
      (node (ref "REL8") (pin "5") (pinfunction "5_5") (pintype "passive"))
    )
    (net (code "46") (name "RELAY_1") (class "Default")
      (node (ref "D1") (pin "A") (pinfunction "A_A") (pintype "passive"))
      (node (ref "R1") (pin "2") (pinfunction "2_2") (pintype "passive"))
      (node (ref "REL1") (pin "1") (pinfunction "1_1") (pintype "passive"))
    )
    (net (code "47") (name "RELAY_2") (class "Default")
      (node (ref "D2") (pin "A") (pinfunction "A_A") (pintype "passive"))
      (node (ref "R2") (pin "2") (pinfunction "2_2") (pintype "passive"))
      (node (ref "REL2") (pin "1") (pinfunction "1_1") (pintype "passive"))
    )
    (net (code "48") (name "RELAY_3") (class "Default")
      (node (ref "D3") (pin "A") (pinfunction "A_A") (pintype "passive"))
      (node (ref "R3") (pin "2") (pinfunction "2_2") (pintype "passive"))
      (node (ref "REL3") (pin "1") (pinfunction "1_1") (pintype "passive"))
    )
    (net (code "49") (name "RELAY_4") (class "Default")
      (node (ref "D4") (pin "A") (pinfunction "A_A") (pintype "passive"))
      (node (ref "R4") (pin "2") (pinfunction "2_2") (pintype "passive"))
      (node (ref "REL4") (pin "1") (pinfunction "1_1") (pintype "passive"))
    )
    (net (code "50") (name "RELAY_5") (class "Default")
      (node (ref "D5") (pin "A") (pinfunction "A_A") (pintype "passive"))
      (node (ref "R5") (pin "2") (pinfunction "2_2") (pintype "passive"))
      (node (ref "REL5") (pin "1") (pinfunction "1_1") (pintype "passive"))
    )
    (net (code "51") (name "RELAY_6") (class "Default")
      (node (ref "D6") (pin "A") (pinfunction "A_A") (pintype "passive"))
      (node (ref "R6") (pin "2") (pinfunction "2_2") (pintype "passive"))
      (node (ref "REL6") (pin "1") (pinfunction "1_1") (pintype "passive"))
    )
    (net (code "52") (name "RELAY_7") (class "Default")
      (node (ref "D7") (pin "A") (pinfunction "A_A") (pintype "passive"))
      (node (ref "R7") (pin "2") (pinfunction "2_2") (pintype "passive"))
      (node (ref "REL7") (pin "1") (pinfunction "1_1") (pintype "passive"))
    )
    (net (code "53") (name "RELAY_8") (class "Default")
      (node (ref "D8") (pin "A") (pinfunction "A_A") (pintype "passive"))
      (node (ref "R8") (pin "2") (pinfunction "2_2") (pintype "passive"))
      (node (ref "REL8") (pin "1") (pinfunction "1_1") (pintype "passive"))
    )
    (net (code "54") (name "REL_0") (class "Default")
      (node (ref "CON1") (pin "12") (pinfunction "12_12") (pintype "bidirectional"))
      (node (ref "IC1") (pin "1") (pinfunction "1B_1") (pintype "bidirectional"))
    )
    (net (code "55") (name "REL_1") (class "Default")
      (node (ref "CON1") (pin "11") (pinfunction "11_11") (pintype "bidirectional"))
      (node (ref "IC1") (pin "2") (pinfunction "2B_2") (pintype "bidirectional"))
    )
    (net (code "56") (name "REL_2") (class "Default")
      (node (ref "CON1") (pin "10") (pinfunction "10_10") (pintype "bidirectional"))
      (node (ref "IC1") (pin "3") (pinfunction "3B_3") (pintype "bidirectional"))
    )
    (net (code "57") (name "REL_3") (class "Default")
      (node (ref "CON1") (pin "9") (pinfunction "9_9") (pintype "bidirectional"))
      (node (ref "IC1") (pin "4") (pinfunction "4B_4") (pintype "bidirectional"))
    )
    (net (code "58") (name "REL_4") (class "Default")
      (node (ref "CON1") (pin "8") (pinfunction "8_8") (pintype "bidirectional"))
      (node (ref "IC1") (pin "5") (pinfunction "5B_5") (pintype "bidirectional"))
    )
    (net (code "59") (name "REL_5") (class "Default")
      (node (ref "CON1") (pin "7") (pinfunction "7_7") (pintype "bidirectional"))
      (node (ref "IC1") (pin "6") (pinfunction "6B_6") (pintype "bidirectional"))
    )
    (net (code "60") (name "REL_6") (class "Default")
      (node (ref "CON1") (pin "6") (pinfunction "6_6") (pintype "bidirectional"))
      (node (ref "IC1") (pin "7") (pinfunction "7B_7") (pintype "bidirectional"))
    )
    (net (code "61") (name "REL_7") (class "Default")
      (node (ref "CON1") (pin "5") (pinfunction "5_5") (pintype "bidirectional"))
      (node (ref "IC1") (pin "8") (pinfunction "8B_8") (pintype "bidirectional"))
    )
    (net (code "62") (name "VMEA{slash}RX") (class "Default")
      (node (ref "CON1") (pin "3") (pinfunction "3_3") (pintype "bidirectional"))
    )
  )
)
